# step_board.net
KiCad netlist of a schematic drawn in EAGLE
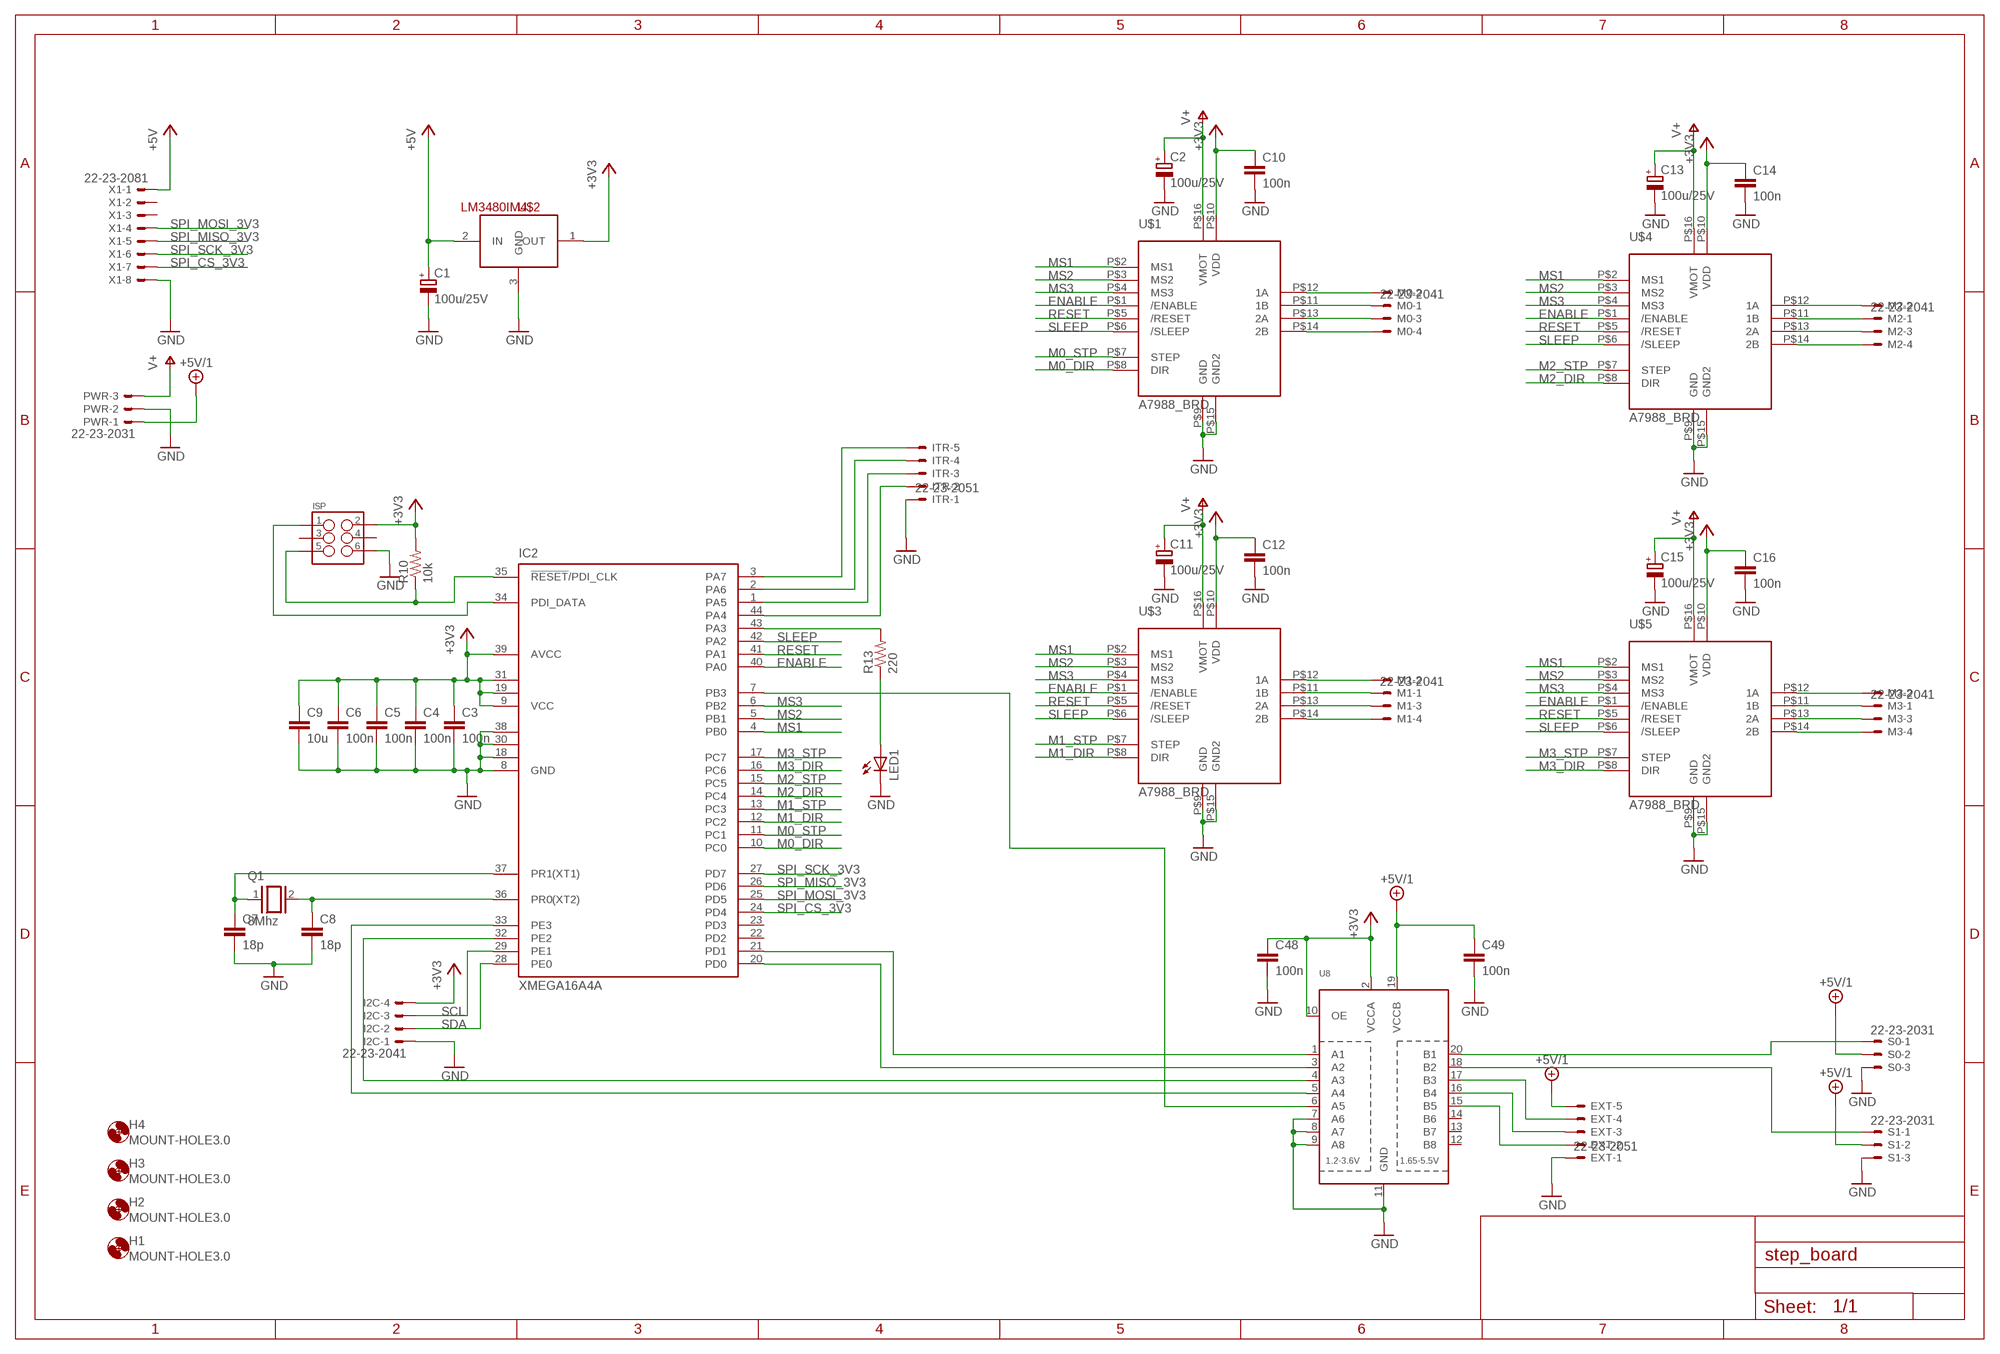
[diagram p0: schematic, sheet 1]

(export (version "E")
  (design (tool "Eeschema 10.0.6"))
  (components
    (comp (ref "C1")
      (value "100u/25V")
      (footprint "eagle-import:PANASONIC_E")
      (libsource (lib "eagle-import") (part "CPOL-EUE"))
    )
    (comp (ref "C2")
      (value "100u/25V")
      (footprint "eagle-import:PANASONIC_E")
      (libsource (lib "eagle-import") (part "CPOL-EUE"))
    )
    (comp (ref "C3")
      (value "100n")
      (footprint "eagle-import:C0603")
      (libsource (lib "eagle-import") (part "C-EUC0603"))
    )
    (comp (ref "C4")
      (value "100n")
      (footprint "eagle-import:C0603")
      (libsource (lib "eagle-import") (part "C-EUC0603"))
    )
    (comp (ref "C5")
      (value "100n")
      (footprint "eagle-import:C0603")
      (libsource (lib "eagle-import") (part "C-EUC0603"))
    )
    (comp (ref "C6")
      (value "100n")
      (footprint "eagle-import:C0603")
      (libsource (lib "eagle-import") (part "C-EUC0603"))
    )
    (comp (ref "C7")
      (value "18p")
      (footprint "eagle-import:C0603")
      (libsource (lib "eagle-import") (part "C-EUC0603"))
    )
    (comp (ref "C8")
      (value "18p")
      (footprint "eagle-import:C0603")
      (libsource (lib "eagle-import") (part "C-EUC0603"))
    )
    (comp (ref "C9")
      (value "10u")
      (footprint "eagle-import:C0805")
      (libsource (lib "eagle-import") (part "C-EUC0805"))
    )
    (comp (ref "C10")
      (value "100n")
      (footprint "eagle-import:C0603")
      (libsource (lib "eagle-import") (part "C-EUC0603"))
    )
    (comp (ref "C11")
      (value "100u/25V")
      (footprint "eagle-import:PANASONIC_E")
      (libsource (lib "eagle-import") (part "CPOL-EUE"))
    )
    (comp (ref "C12")
      (value "100n")
      (footprint "eagle-import:C0603")
      (libsource (lib "eagle-import") (part "C-EUC0603"))
    )
    (comp (ref "C13")
      (value "100u/25V")
      (footprint "eagle-import:PANASONIC_E")
      (libsource (lib "eagle-import") (part "CPOL-EUE"))
    )
    (comp (ref "C14")
      (value "100n")
      (footprint "eagle-import:C0603")
      (libsource (lib "eagle-import") (part "C-EUC0603"))
    )
    (comp (ref "C15")
      (value "100u/25V")
      (footprint "eagle-import:PANASONIC_E")
      (libsource (lib "eagle-import") (part "CPOL-EUE"))
    )
    (comp (ref "C16")
      (value "100n")
      (footprint "eagle-import:C0603")
      (libsource (lib "eagle-import") (part "C-EUC0603"))
    )
    (comp (ref "C48")
      (value "100n")
      (footprint "eagle-import:C0603K")
      (libsource (lib "eagle-import") (part "C-EUC0603K"))
    )
    (comp (ref "C49")
      (value "100n")
      (footprint "eagle-import:C0603K")
      (libsource (lib "eagle-import") (part "C-EUC0603K"))
    )
    (comp (ref "EXT")
      (value "22-23-2051")
      (footprint "eagle-import:22-23-2051")
      (fields (field (name "MF") "MOLEX"))
      (libsource (lib "eagle-import") (part "22-23-2051"))
    )
    (comp (ref "H1")
      (value "MOUNT-HOLE3.0")
      (footprint "eagle-import:3,0")
      (libsource (lib "eagle-import") (part "MOUNT-HOLE3.0"))
    )
    (comp (ref "H2")
      (value "MOUNT-HOLE3.0")
      (footprint "eagle-import:3,0")
      (libsource (lib "eagle-import") (part "MOUNT-HOLE3.0"))
    )
    (comp (ref "H3")
      (value "MOUNT-HOLE3.0")
      (footprint "eagle-import:3,0")
      (libsource (lib "eagle-import") (part "MOUNT-HOLE3.0"))
    )
    (comp (ref "H4")
      (value "MOUNT-HOLE3.0")
      (footprint "eagle-import:3,0")
      (libsource (lib "eagle-import") (part "MOUNT-HOLE3.0"))
    )
    (comp (ref "I2C")
      (value "22-23-2041")
      (footprint "eagle-import:22-23-2041")
      (fields (field (name "MF") "MOLEX"))
      (libsource (lib "eagle-import") (part "22-23-2041"))
    )
    (comp (ref "IC2")
      (value "XMEGA16A4A")
      (footprint "eagle-import:TQFP44")
      (libsource (lib "eagle-import") (part "XMEGA16A4A"))
    )
    (comp (ref "ISP")
      (value "M03X2POGO_PINS")
      (footprint "eagle-import:2X3_POGO")
      (libsource (lib "eagle-import") (part "M03X2POGO_PINS"))
    )
    (comp (ref "ITR")
      (value "22-23-2051")
      (footprint "eagle-import:22-23-2051")
      (fields (field (name "MF") "MOLEX"))
      (libsource (lib "eagle-import") (part "22-23-2051"))
    )
    (comp (ref "LED1")
      (value "LEDCHIP-LED0603")
      (footprint "eagle-import:CHIP-LED0603")
      (libsource (lib "eagle-import") (part "LEDCHIP-LED0603"))
    )
    (comp (ref "M0")
      (value "22-23-2041")
      (footprint "eagle-import:22-23-2041")
      (fields (field (name "MF") "MOLEX"))
      (libsource (lib "eagle-import") (part "22-23-2041"))
    )
    (comp (ref "M1")
      (value "22-23-2041")
      (footprint "eagle-import:22-23-2041")
      (fields (field (name "MF") "MOLEX"))
      (libsource (lib "eagle-import") (part "22-23-2041"))
    )
    (comp (ref "M2")
      (value "22-23-2041")
      (footprint "eagle-import:22-23-2041")
      (fields (field (name "MF") "MOLEX"))
      (libsource (lib "eagle-import") (part "22-23-2041"))
    )
    (comp (ref "M3")
      (value "22-23-2041")
      (footprint "eagle-import:22-23-2041")
      (fields (field (name "MF") "MOLEX"))
      (libsource (lib "eagle-import") (part "22-23-2041"))
    )
    (comp (ref "PWR")
      (value "22-23-2031")
      (footprint "eagle-import:22-23-2031")
      (fields (field (name "MF") "MOLEX"))
      (libsource (lib "eagle-import") (part "22-23-2031"))
    )
    (comp (ref "Q1")
      (value "8Mhz")
      (footprint "eagle-import:QS")
      (libsource (lib "eagle-import") (part "XTAL/S"))
    )
    (comp (ref "R10")
      (value "10k")
      (footprint "eagle-import:R0603")
      (libsource (lib "eagle-import") (part "R-US_R0603"))
    )
    (comp (ref "R13")
      (value "220")
      (footprint "eagle-import:R0603")
      (libsource (lib "eagle-import") (part "R-US_R0603"))
    )
    (comp (ref "S0")
      (value "22-23-2031")
      (footprint "eagle-import:22-23-2031")
      (fields (field (name "MF") "MOLEX"))
      (libsource (lib "eagle-import") (part "22-23-2031"))
    )
    (comp (ref "S1")
      (value "22-23-2031")
      (footprint "eagle-import:22-23-2031")
      (fields (field (name "MF") "MOLEX"))
      (libsource (lib "eagle-import") (part "22-23-2031"))
    )
    (comp (ref "U$1")
      (value "A7988_BRD")
      (footprint "eagle-import:A4988_BRD")
      (libsource (lib "eagle-import") (part "A7988_BRD"))
    )
    (comp (ref "U$2")
      (value "LM3480IM4")
      (footprint "eagle-import:SOT23-3")
      (libsource (lib "eagle-import") (part "LM3480IM4"))
    )
    (comp (ref "U$3")
      (value "A7988_BRD")
      (footprint "eagle-import:A4988_BRD")
      (libsource (lib "eagle-import") (part "A7988_BRD"))
    )
    (comp (ref "U$4")
      (value "A7988_BRD")
      (footprint "eagle-import:A4988_BRD")
      (libsource (lib "eagle-import") (part "A7988_BRD"))
    )
    (comp (ref "U$5")
      (value "A7988_BRD")
      (footprint "eagle-import:A4988_BRD")
      (libsource (lib "eagle-import") (part "A7988_BRD"))
    )
    (comp (ref "U8")
      (value "TXB0108PWR")
      (footprint "eagle-import:TSSOP20")
      (libsource (lib "eagle-import") (part "TXB0108PWR"))
    )
    (comp (ref "X1")
      (value "22-23-2081")
      (footprint "eagle-import:22-23-2081")
      (fields (field (name "MF") "MOLEX"))
      (libsource (lib "eagle-import") (part "22-23-2081"))
    )
  )
  (nets
    (net (code "1") (name "+3V3") (class "Default")
      (node (ref "C10") (pin "1") (pinfunction "1_1") (pintype "passive"))
      (node (ref "C12") (pin "1") (pinfunction "1_1") (pintype "passive"))
      (node (ref "C14") (pin "1") (pinfunction "1_1") (pintype "passive"))
      (node (ref "C16") (pin "1") (pinfunction "1_1") (pintype "passive"))
      (node (ref "C3") (pin "1") (pinfunction "1_1") (pintype "passive"))
      (node (ref "C4") (pin "1") (pinfunction "1_1") (pintype "passive"))
      (node (ref "C48") (pin "1") (pinfunction "1_1") (pintype "passive"))
      (node (ref "C5") (pin "1") (pinfunction "1_1") (pintype "passive"))
      (node (ref "C6") (pin "1") (pinfunction "1_1") (pintype "passive"))
      (node (ref "C9") (pin "1") (pinfunction "1_1") (pintype "passive"))
      (node (ref "I2C") (pin "4") (pinfunction "S_4") (pintype "passive"))
      (node (ref "IC2") (pin "19") (pinfunction "VCC1_19") (pintype "power_in"))
      (node (ref "IC2") (pin "31") (pinfunction "VCC2_31") (pintype "power_in"))
      (node (ref "IC2") (pin "39") (pinfunction "AVCC_39") (pintype "power_in"))
      (node (ref "IC2") (pin "9") (pinfunction "VCC_9") (pintype "power_in"))
      (node (ref "ISP") (pin "P$2") (pinfunction "2_P$2") (pintype "bidirectional"))
      (node (ref "R10") (pin "2") (pinfunction "2_2") (pintype "passive"))
      (node (ref "U$1") (pin "P$10") (pinfunction "VDD_P$10") (pintype "bidirectional"))
      (node (ref "U$2") (pin "1") (pinfunction "OUT_1") (pintype "bidirectional"))
      (node (ref "U$3") (pin "P$10") (pinfunction "VDD_P$10") (pintype "bidirectional"))
      (node (ref "U$4") (pin "P$10") (pinfunction "VDD_P$10") (pintype "bidirectional"))
      (node (ref "U$5") (pin "P$10") (pinfunction "VDD_P$10") (pintype "bidirectional"))
      (node (ref "U8") (pin "10") (pinfunction "OE_10") (pintype "bidirectional"))
      (node (ref "U8") (pin "2") (pinfunction "VCCA_2") (pintype "bidirectional"))
    )
    (net (code "2") (name "+5V") (class "Default")
      (node (ref "C1") (pin "+") (pinfunction "+_+") (pintype "passive"))
      (node (ref "U$2") (pin "2") (pinfunction "IN_2") (pintype "bidirectional"))
      (node (ref "X1") (pin "1") (pinfunction "S_1") (pintype "passive"))
    )
    (net (code "3") (name "+5V{slash}1") (class "Default")
      (node (ref "C49") (pin "1") (pinfunction "1_1") (pintype "passive"))
      (node (ref "EXT") (pin "5") (pinfunction "S_5") (pintype "passive"))
      (node (ref "PWR") (pin "1") (pinfunction "S_1") (pintype "passive"))
      (node (ref "S0") (pin "2") (pinfunction "S_2") (pintype "passive"))
      (node (ref "S1") (pin "2") (pinfunction "S_2") (pintype "passive"))
      (node (ref "U8") (pin "19") (pinfunction "VCCB_19") (pintype "bidirectional"))
    )
    (net (code "4") (name "/ENABLE") (class "Default")
      (node (ref "IC2") (pin "40") (pinfunction "PA0_40") (pintype "bidirectional"))
      (node (ref "U$1") (pin "P$1") (pinfunction "/ENABLE_P$1") (pintype "bidirectional"))
      (node (ref "U$3") (pin "P$1") (pinfunction "/ENABLE_P$1") (pintype "bidirectional"))
      (node (ref "U$4") (pin "P$1") (pinfunction "/ENABLE_P$1") (pintype "bidirectional"))
      (node (ref "U$5") (pin "P$1") (pinfunction "/ENABLE_P$1") (pintype "bidirectional"))
    )
    (net (code "5") (name "/M0_DIR") (class "Default")
      (node (ref "IC2") (pin "10") (pinfunction "PC0_10") (pintype "bidirectional"))
      (node (ref "U$1") (pin "P$8") (pinfunction "DIR_P$8") (pintype "bidirectional"))
    )
    (net (code "6") (name "/M0_STP") (class "Default")
      (node (ref "IC2") (pin "11") (pinfunction "PC1_11") (pintype "bidirectional"))
      (node (ref "U$1") (pin "P$7") (pinfunction "STEP_P$7") (pintype "bidirectional"))
    )
    (net (code "7") (name "/M1_DIR") (class "Default")
      (node (ref "IC2") (pin "12") (pinfunction "PC2_12") (pintype "bidirectional"))
      (node (ref "U$3") (pin "P$8") (pinfunction "DIR_P$8") (pintype "bidirectional"))
    )
    (net (code "8") (name "/M1_STP") (class "Default")
      (node (ref "IC2") (pin "13") (pinfunction "PC3_13") (pintype "bidirectional"))
      (node (ref "U$3") (pin "P$7") (pinfunction "STEP_P$7") (pintype "bidirectional"))
    )
    (net (code "9") (name "/M2_DIR") (class "Default")
      (node (ref "IC2") (pin "14") (pinfunction "PC4_14") (pintype "bidirectional"))
      (node (ref "U$4") (pin "P$8") (pinfunction "DIR_P$8") (pintype "bidirectional"))
    )
    (net (code "10") (name "/M2_STP") (class "Default")
      (node (ref "IC2") (pin "15") (pinfunction "PC5_15") (pintype "bidirectional"))
      (node (ref "U$4") (pin "P$7") (pinfunction "STEP_P$7") (pintype "bidirectional"))
    )
    (net (code "11") (name "/M3_DIR") (class "Default")
      (node (ref "IC2") (pin "16") (pinfunction "PC6_16") (pintype "bidirectional"))
      (node (ref "U$5") (pin "P$8") (pinfunction "DIR_P$8") (pintype "bidirectional"))
    )
    (net (code "12") (name "/M3_STP") (class "Default")
      (node (ref "IC2") (pin "17") (pinfunction "PC7_17") (pintype "bidirectional"))
      (node (ref "U$5") (pin "P$7") (pinfunction "STEP_P$7") (pintype "bidirectional"))
    )
    (net (code "13") (name "/MS1") (class "Default")
      (node (ref "IC2") (pin "4") (pinfunction "PB0_4") (pintype "bidirectional"))
      (node (ref "U$1") (pin "P$2") (pinfunction "MS1_P$2") (pintype "bidirectional"))
      (node (ref "U$3") (pin "P$2") (pinfunction "MS1_P$2") (pintype "bidirectional"))
      (node (ref "U$4") (pin "P$2") (pinfunction "MS1_P$2") (pintype "bidirectional"))
      (node (ref "U$5") (pin "P$2") (pinfunction "MS1_P$2") (pintype "bidirectional"))
    )
    (net (code "14") (name "/MS2") (class "Default")
      (node (ref "IC2") (pin "5") (pinfunction "PB1_5") (pintype "bidirectional"))
      (node (ref "U$1") (pin "P$3") (pinfunction "MS2_P$3") (pintype "bidirectional"))
      (node (ref "U$3") (pin "P$3") (pinfunction "MS2_P$3") (pintype "bidirectional"))
      (node (ref "U$4") (pin "P$3") (pinfunction "MS2_P$3") (pintype "bidirectional"))
      (node (ref "U$5") (pin "P$3") (pinfunction "MS2_P$3") (pintype "bidirectional"))
    )
    (net (code "15") (name "/MS3") (class "Default")
      (node (ref "IC2") (pin "6") (pinfunction "PB2_6") (pintype "bidirectional"))
      (node (ref "U$1") (pin "P$4") (pinfunction "MS3_P$4") (pintype "bidirectional"))
      (node (ref "U$3") (pin "P$4") (pinfunction "MS3_P$4") (pintype "bidirectional"))
      (node (ref "U$4") (pin "P$4") (pinfunction "MS3_P$4") (pintype "bidirectional"))
      (node (ref "U$5") (pin "P$4") (pinfunction "MS3_P$4") (pintype "bidirectional"))
    )
    (net (code "16") (name "/RESET") (class "Default")
      (node (ref "IC2") (pin "41") (pinfunction "PA1_41") (pintype "bidirectional"))
      (node (ref "U$1") (pin "P$5") (pinfunction "/RESET_P$5") (pintype "bidirectional"))
      (node (ref "U$3") (pin "P$5") (pinfunction "/RESET_P$5") (pintype "bidirectional"))
      (node (ref "U$4") (pin "P$5") (pinfunction "/RESET_P$5") (pintype "bidirectional"))
      (node (ref "U$5") (pin "P$5") (pinfunction "/RESET_P$5") (pintype "bidirectional"))
    )
    (net (code "17") (name "/SCL") (class "Default")
      (node (ref "I2C") (pin "3") (pinfunction "S_3") (pintype "passive"))
      (node (ref "IC2") (pin "29") (pinfunction "PE1_29") (pintype "bidirectional"))
    )
    (net (code "18") (name "/SDA") (class "Default")
      (node (ref "I2C") (pin "2") (pinfunction "S_2") (pintype "passive"))
      (node (ref "IC2") (pin "28") (pinfunction "PE0_28") (pintype "bidirectional"))
    )
    (net (code "19") (name "/SLEEP") (class "Default")
      (node (ref "IC2") (pin "42") (pinfunction "PA2_42") (pintype "bidirectional"))
      (node (ref "U$1") (pin "P$6") (pinfunction "/SLEEP_P$6") (pintype "bidirectional"))
      (node (ref "U$3") (pin "P$6") (pinfunction "/SLEEP_P$6") (pintype "bidirectional"))
      (node (ref "U$4") (pin "P$6") (pinfunction "/SLEEP_P$6") (pintype "bidirectional"))
      (node (ref "U$5") (pin "P$6") (pinfunction "/SLEEP_P$6") (pintype "bidirectional"))
    )
    (net (code "20") (name "/SPI_CS_3V3") (class "Default")
      (node (ref "IC2") (pin "24") (pinfunction "PD4_24") (pintype "bidirectional"))
      (node (ref "X1") (pin "7") (pinfunction "S_7") (pintype "passive"))
    )
    (net (code "21") (name "/SPI_MISO_3V3") (class "Default")
      (node (ref "IC2") (pin "26") (pinfunction "PD6_26") (pintype "bidirectional"))
      (node (ref "X1") (pin "5") (pinfunction "S_5") (pintype "passive"))
    )
    (net (code "22") (name "/SPI_MOSI_3V3") (class "Default")
      (node (ref "IC2") (pin "25") (pinfunction "PD5_25") (pintype "bidirectional"))
      (node (ref "X1") (pin "4") (pinfunction "S_4") (pintype "passive"))
    )
    (net (code "23") (name "/SPI_SCK_3V3") (class "Default")
      (node (ref "IC2") (pin "27") (pinfunction "PD7_27") (pintype "bidirectional"))
      (node (ref "X1") (pin "6") (pinfunction "S_6") (pintype "passive"))
    )
    (net (code "24") (name "GND") (class "Default")
      (node (ref "C1") (pin "-") (pinfunction "-_-") (pintype "passive"))
      (node (ref "C10") (pin "2") (pinfunction "2_2") (pintype "passive"))
      (node (ref "C11") (pin "-") (pinfunction "-_-") (pintype "passive"))
      (node (ref "C12") (pin "2") (pinfunction "2_2") (pintype "passive"))
      (node (ref "C13") (pin "-") (pinfunction "-_-") (pintype "passive"))
      (node (ref "C14") (pin "2") (pinfunction "2_2") (pintype "passive"))
      (node (ref "C15") (pin "-") (pinfunction "-_-") (pintype "passive"))
      (node (ref "C16") (pin "2") (pinfunction "2_2") (pintype "passive"))
      (node (ref "C2") (pin "-") (pinfunction "-_-") (pintype "passive"))
      (node (ref "C3") (pin "2") (pinfunction "2_2") (pintype "passive"))
      (node (ref "C4") (pin "2") (pinfunction "2_2") (pintype "passive"))
      (node (ref "C48") (pin "2") (pinfunction "2_2") (pintype "passive"))
      (node (ref "C49") (pin "2") (pinfunction "2_2") (pintype "passive"))
      (node (ref "C5") (pin "2") (pinfunction "2_2") (pintype "passive"))
      (node (ref "C6") (pin "2") (pinfunction "2_2") (pintype "passive"))
      (node (ref "C7") (pin "2") (pinfunction "2_2") (pintype "passive"))
      (node (ref "C8") (pin "2") (pinfunction "2_2") (pintype "passive"))
      (node (ref "C9") (pin "2") (pinfunction "2_2") (pintype "passive"))
      (node (ref "EXT") (pin "1") (pinfunction "S_1") (pintype "passive"))
      (node (ref "I2C") (pin "1") (pinfunction "S_1") (pintype "passive"))
      (node (ref "IC2") (pin "18") (pinfunction "GND1_18") (pintype "power_in"))
      (node (ref "IC2") (pin "30") (pinfunction "GND2_30") (pintype "power_in"))
      (node (ref "IC2") (pin "38") (pinfunction "GND3_38") (pintype "power_in"))
      (node (ref "IC2") (pin "8") (pinfunction "GND_8") (pintype "power_in"))
      (node (ref "ISP") (pin "P$6") (pinfunction "6_P$6") (pintype "bidirectional"))
      (node (ref "ITR") (pin "1") (pinfunction "S_1") (pintype "passive"))
      (node (ref "LED1") (pin "C") (pinfunction "C_C") (pintype "passive"))
      (node (ref "PWR") (pin "2") (pinfunction "S_2") (pintype "passive"))
      (node (ref "S0") (pin "3") (pinfunction "S_3") (pintype "passive"))
      (node (ref "S1") (pin "3") (pinfunction "S_3") (pintype "passive"))
      (node (ref "U$1") (pin "P$15") (pinfunction "GND2_P$15") (pintype "bidirectional"))
      (node (ref "U$1") (pin "P$9") (pinfunction "GND_P$9") (pintype "bidirectional"))
      (node (ref "U$2") (pin "3") (pinfunction "GND_3") (pintype "bidirectional"))
      (node (ref "U$3") (pin "P$15") (pinfunction "GND2_P$15") (pintype "bidirectional"))
      (node (ref "U$3") (pin "P$9") (pinfunction "GND_P$9") (pintype "bidirectional"))
      (node (ref "U$4") (pin "P$15") (pinfunction "GND2_P$15") (pintype "bidirectional"))
      (node (ref "U$4") (pin "P$9") (pinfunction "GND_P$9") (pintype "bidirectional"))
      (node (ref "U$5") (pin "P$15") (pinfunction "GND2_P$15") (pintype "bidirectional"))
      (node (ref "U$5") (pin "P$9") (pinfunction "GND_P$9") (pintype "bidirectional"))
      (node (ref "U8") (pin "11") (pinfunction "GND_11") (pintype "bidirectional"))
      (node (ref "U8") (pin "7") (pinfunction "A6_7") (pintype "bidirectional"))
      (node (ref "U8") (pin "8") (pinfunction "A7_8") (pintype "bidirectional"))
      (node (ref "U8") (pin "9") (pinfunction "A8_9") (pintype "bidirectional"))
      (node (ref "X1") (pin "8") (pinfunction "S_8") (pintype "passive"))
    )
    (net (code "25") (name "Net-(EXTB-S)") (class "Default")
      (node (ref "EXT") (pin "2") (pinfunction "S_2") (pintype "passive"))
      (node (ref "U8") (pin "15") (pinfunction "B5_15") (pintype "bidirectional"))
    )
    (net (code "26") (name "Net-(EXTC-S)") (class "Default")
      (node (ref "EXT") (pin "3") (pinfunction "S_3") (pintype "passive"))
      (node (ref "U8") (pin "16") (pinfunction "B4_16") (pintype "bidirectional"))
    )
    (net (code "27") (name "Net-(EXTD-S)") (class "Default")
      (node (ref "EXT") (pin "4") (pinfunction "S_4") (pintype "passive"))
      (node (ref "U8") (pin "17") (pinfunction "B3_17") (pintype "bidirectional"))
    )
    (net (code "28") (name "Net-(IC2-PA3)") (class "Default")
      (node (ref "IC2") (pin "43") (pinfunction "PA3_43") (pintype "bidirectional"))
      (node (ref "R13") (pin "2") (pinfunction "2_2") (pintype "passive"))
    )
    (net (code "29") (name "Net-(IC2-PA4)") (class "Default")
      (node (ref "IC2") (pin "44") (pinfunction "PA4_44") (pintype "bidirectional"))
      (node (ref "ITR") (pin "2") (pinfunction "S_2") (pintype "passive"))
    )
    (net (code "30") (name "Net-(IC2-PA5)") (class "Default")
      (node (ref "IC2") (pin "1") (pinfunction "PA5_1") (pintype "bidirectional"))
      (node (ref "ITR") (pin "3") (pinfunction "S_3") (pintype "passive"))
    )
    (net (code "31") (name "Net-(IC2-PA6)") (class "Default")
      (node (ref "IC2") (pin "2") (pinfunction "PA6_2") (pintype "bidirectional"))
      (node (ref "ITR") (pin "4") (pinfunction "S_4") (pintype "passive"))
    )
    (net (code "32") (name "Net-(IC2-PA7)") (class "Default")
      (node (ref "IC2") (pin "3") (pinfunction "PA7_3") (pintype "bidirectional"))
      (node (ref "ITR") (pin "5") (pinfunction "S_5") (pintype "passive"))
    )
    (net (code "33") (name "Net-(IC2-PB3)") (class "Default")
      (node (ref "IC2") (pin "7") (pinfunction "PB3_7") (pintype "bidirectional"))
      (node (ref "U8") (pin "6") (pinfunction "A5_6") (pintype "bidirectional"))
    )
    (net (code "34") (name "Net-(IC2-PD0)") (class "Default")
      (node (ref "IC2") (pin "20") (pinfunction "PD0_20") (pintype "bidirectional"))
      (node (ref "U8") (pin "3") (pinfunction "A2_3") (pintype "bidirectional"))
    )
    (net (code "35") (name "Net-(IC2-PD1)") (class "Default")
      (node (ref "IC2") (pin "21") (pinfunction "PD1_21") (pintype "bidirectional"))
      (node (ref "U8") (pin "1") (pinfunction "A1_1") (pintype "bidirectional"))
    )
    (net (code "36") (name "Net-(IC2-PDI_DATA)") (class "Default")
      (node (ref "IC2") (pin "34") (pinfunction "PDI_DATA_34") (pintype "bidirectional"))
      (node (ref "ISP") (pin "P$1") (pinfunction "1_P$1") (pintype "bidirectional"))
    )
    (net (code "37") (name "Net-(IC2-PE2)") (class "Default")
      (node (ref "IC2") (pin "32") (pinfunction "PE2_32") (pintype "bidirectional"))
      (node (ref "U8") (pin "4") (pinfunction "A3_4") (pintype "bidirectional"))
    )
    (net (code "38") (name "Net-(IC2-PE3)") (class "Default")
      (node (ref "IC2") (pin "33") (pinfunction "PE3_33") (pintype "bidirectional"))
      (node (ref "U8") (pin "5") (pinfunction "A4_5") (pintype "bidirectional"))
    )
    (net (code "39") (name "Net-(IC2-PR0(XT2))") (class "Default")
      (node (ref "C8") (pin "1") (pinfunction "1_1") (pintype "passive"))
      (node (ref "IC2") (pin "36") (pinfunction "PR0(XT2)_36") (pintype "bidirectional"))
      (node (ref "Q1") (pin "2") (pinfunction "2_2") (pintype "passive"))
    )
    (net (code "40") (name "Net-(IC2-PR1(XT1))") (class "Default")
      (node (ref "C7") (pin "1") (pinfunction "1_1") (pintype "passive"))
      (node (ref "IC2") (pin "37") (pinfunction "PR1(XT1)_37") (pintype "bidirectional"))
      (node (ref "Q1") (pin "1") (pinfunction "1_1") (pintype "passive"))
    )
    (net (code "41") (name "Net-(IC2-~{RESET}{slash}PDI_CLK)") (class "Default")
      (node (ref "IC2") (pin "35") (pinfunction "~{RESET}/PDI_CLK_35") (pintype "bidirectional"))
      (node (ref "ISP") (pin "P$5") (pinfunction "5_P$5") (pintype "bidirectional"))
      (node (ref "R10") (pin "1") (pinfunction "1_1") (pintype "passive"))
    )
    (net (code "42") (name "Net-(LED1-PadA)") (class "Default")
      (node (ref "LED1") (pin "A") (pinfunction "A_A") (pintype "passive"))
      (node (ref "R13") (pin "1") (pinfunction "1_1") (pintype "passive"))
    )
    (net (code "43") (name "Net-(M0A-S)") (class "Default")
      (node (ref "M0") (pin "1") (pinfunction "S_1") (pintype "passive"))
      (node (ref "U$1") (pin "P$11") (pinfunction "1B_P$11") (pintype "bidirectional"))
    )
    (net (code "44") (name "Net-(M0B-S)") (class "Default")
      (node (ref "M0") (pin "2") (pinfunction "S_2") (pintype "passive"))
      (node (ref "U$1") (pin "P$12") (pinfunction "1A_P$12") (pintype "bidirectional"))
    )
    (net (code "45") (name "Net-(M0C-S)") (class "Default")
      (node (ref "M0") (pin "3") (pinfunction "S_3") (pintype "passive"))
      (node (ref "U$1") (pin "P$13") (pinfunction "2A_P$13") (pintype "bidirectional"))
    )
    (net (code "46") (name "Net-(M0D-S)") (class "Default")
      (node (ref "M0") (pin "4") (pinfunction "S_4") (pintype "passive"))
      (node (ref "U$1") (pin "P$14") (pinfunction "2B_P$14") (pintype "bidirectional"))
    )
    (net (code "47") (name "Net-(M1A-S)") (class "Default")
      (node (ref "M1") (pin "1") (pinfunction "S_1") (pintype "passive"))
      (node (ref "U$3") (pin "P$11") (pinfunction "1B_P$11") (pintype "bidirectional"))
    )
    (net (code "48") (name "Net-(M1B-S)") (class "Default")
      (node (ref "M1") (pin "2") (pinfunction "S_2") (pintype "passive"))
      (node (ref "U$3") (pin "P$12") (pinfunction "1A_P$12") (pintype "bidirectional"))
    )
    (net (code "49") (name "Net-(M1C-S)") (class "Default")
      (node (ref "M1") (pin "3") (pinfunction "S_3") (pintype "passive"))
      (node (ref "U$3") (pin "P$13") (pinfunction "2A_P$13") (pintype "bidirectional"))
    )
    (net (code "50") (name "Net-(M1D-S)") (class "Default")
      (node (ref "M1") (pin "4") (pinfunction "S_4") (pintype "passive"))
      (node (ref "U$3") (pin "P$14") (pinfunction "2B_P$14") (pintype "bidirectional"))
    )
    (net (code "51") (name "Net-(M2A-S)") (class "Default")
      (node (ref "M2") (pin "1") (pinfunction "S_1") (pintype "passive"))
      (node (ref "U$4") (pin "P$11") (pinfunction "1B_P$11") (pintype "bidirectional"))
    )
    (net (code "52") (name "Net-(M2B-S)") (class "Default")
      (node (ref "M2") (pin "2") (pinfunction "S_2") (pintype "passive"))
      (node (ref "U$4") (pin "P$12") (pinfunction "1A_P$12") (pintype "bidirectional"))
    )
    (net (code "53") (name "Net-(M2C-S)") (class "Default")
      (node (ref "M2") (pin "3") (pinfunction "S_3") (pintype "passive"))
      (node (ref "U$4") (pin "P$13") (pinfunction "2A_P$13") (pintype "bidirectional"))
    )
    (net (code "54") (name "Net-(M2D-S)") (class "Default")
      (node (ref "M2") (pin "4") (pinfunction "S_4") (pintype "passive"))
      (node (ref "U$4") (pin "P$14") (pinfunction "2B_P$14") (pintype "bidirectional"))
    )
    (net (code "55") (name "Net-(M3A-S)") (class "Default")
      (node (ref "M3") (pin "1") (pinfunction "S_1") (pintype "passive"))
      (node (ref "U$5") (pin "P$11") (pinfunction "1B_P$11") (pintype "bidirectional"))
    )
    (net (code "56") (name "Net-(M3B-S)") (class "Default")
      (node (ref "M3") (pin "2") (pinfunction "S_2") (pintype "passive"))
      (node (ref "U$5") (pin "P$12") (pinfunction "1A_P$12") (pintype "bidirectional"))
    )
    (net (code "57") (name "Net-(M3C-S)") (class "Default")
      (node (ref "M3") (pin "3") (pinfunction "S_3") (pintype "passive"))
      (node (ref "U$5") (pin "P$13") (pinfunction "2A_P$13") (pintype "bidirectional"))
    )
    (net (code "58") (name "Net-(M3D-S)") (class "Default")
      (node (ref "M3") (pin "4") (pinfunction "S_4") (pintype "passive"))
      (node (ref "U$5") (pin "P$14") (pinfunction "2B_P$14") (pintype "bidirectional"))
    )
    (net (code "59") (name "Net-(S0A-S)") (class "Default")
      (node (ref "S0") (pin "1") (pinfunction "S_1") (pintype "passive"))
      (node (ref "U8") (pin "20") (pinfunction "B1_20") (pintype "bidirectional"))
    )
    (net (code "60") (name "Net-(S1A-S)") (class "Default")
      (node (ref "S1") (pin "1") (pinfunction "S_1") (pintype "passive"))
      (node (ref "U8") (pin "18") (pinfunction "B2_18") (pintype "bidirectional"))
    )
    (net (code "61") (name "V+") (class "Default")
      (node (ref "C11") (pin "+") (pinfunction "+_+") (pintype "passive"))
      (node (ref "C13") (pin "+") (pinfunction "+_+") (pintype "passive"))
      (node (ref "C15") (pin "+") (pinfunction "+_+") (pintype "passive"))
      (node (ref "C2") (pin "+") (pinfunction "+_+") (pintype "passive"))
      (node (ref "PWR") (pin "3") (pinfunction "S_3") (pintype "passive"))
      (node (ref "U$1") (pin "P$16") (pinfunction "VMOT_P$16") (pintype "bidirectional"))
      (node (ref "U$3") (pin "P$16") (pinfunction "VMOT_P$16") (pintype "bidirectional"))
      (node (ref "U$4") (pin "P$16") (pinfunction "VMOT_P$16") (pintype "bidirectional"))
      (node (ref "U$5") (pin "P$16") (pinfunction "VMOT_P$16") (pintype "bidirectional"))
    )
    (net (code "62") (name "unconnected-(IC2-PD2-Pad22)") (class "Default")
      (node (ref "IC2") (pin "22") (pinfunction "PD2_22") (pintype "bidirectional"))
    )
    (net (code "63") (name "unconnected-(IC2-PD3-Pad23)") (class "Default")
      (node (ref "IC2") (pin "23") (pinfunction "PD3_23") (pintype "bidirectional"))
    )
    (net (code "64") (name "unconnected-(ISP-3-PadP$3)") (class "Default")
      (node (ref "ISP") (pin "P$3") (pinfunction "3_P$3") (pintype "bidirectional"))
    )
    (net (code "65") (name "unconnected-(ISP-4-PadP$4)") (class "Default")
      (node (ref "ISP") (pin "P$4") (pinfunction "4_P$4") (pintype "bidirectional"))
    )
    (net (code "66") (name "unconnected-(U8-B6-Pad14)") (class "Default")
      (node (ref "U8") (pin "14") (pinfunction "B6_14") (pintype "bidirectional"))
    )
    (net (code "67") (name "unconnected-(U8-B7-Pad13)") (class "Default")
      (node (ref "U8") (pin "13") (pinfunction "B7_13") (pintype "bidirectional"))
    )
    (net (code "68") (name "unconnected-(U8-B8-Pad12)") (class "Default")
      (node (ref "U8") (pin "12") (pinfunction "B8_12") (pintype "bidirectional"))
    )
    (net (code "69") (name "unconnected-(X1B-S-Pad2)") (class "Default")
      (node (ref "X1") (pin "2") (pinfunction "S_2") (pintype "passive"))
    )
    (net (code "70") (name "unconnected-(X1C-S-Pad3)") (class "Default")
      (node (ref "X1") (pin "3") (pinfunction "S_3") (pintype "passive"))
    )
  )
)
